# MEGA2560_Rev3e.net
KiCad netlist of a schematic drawn in EAGLE
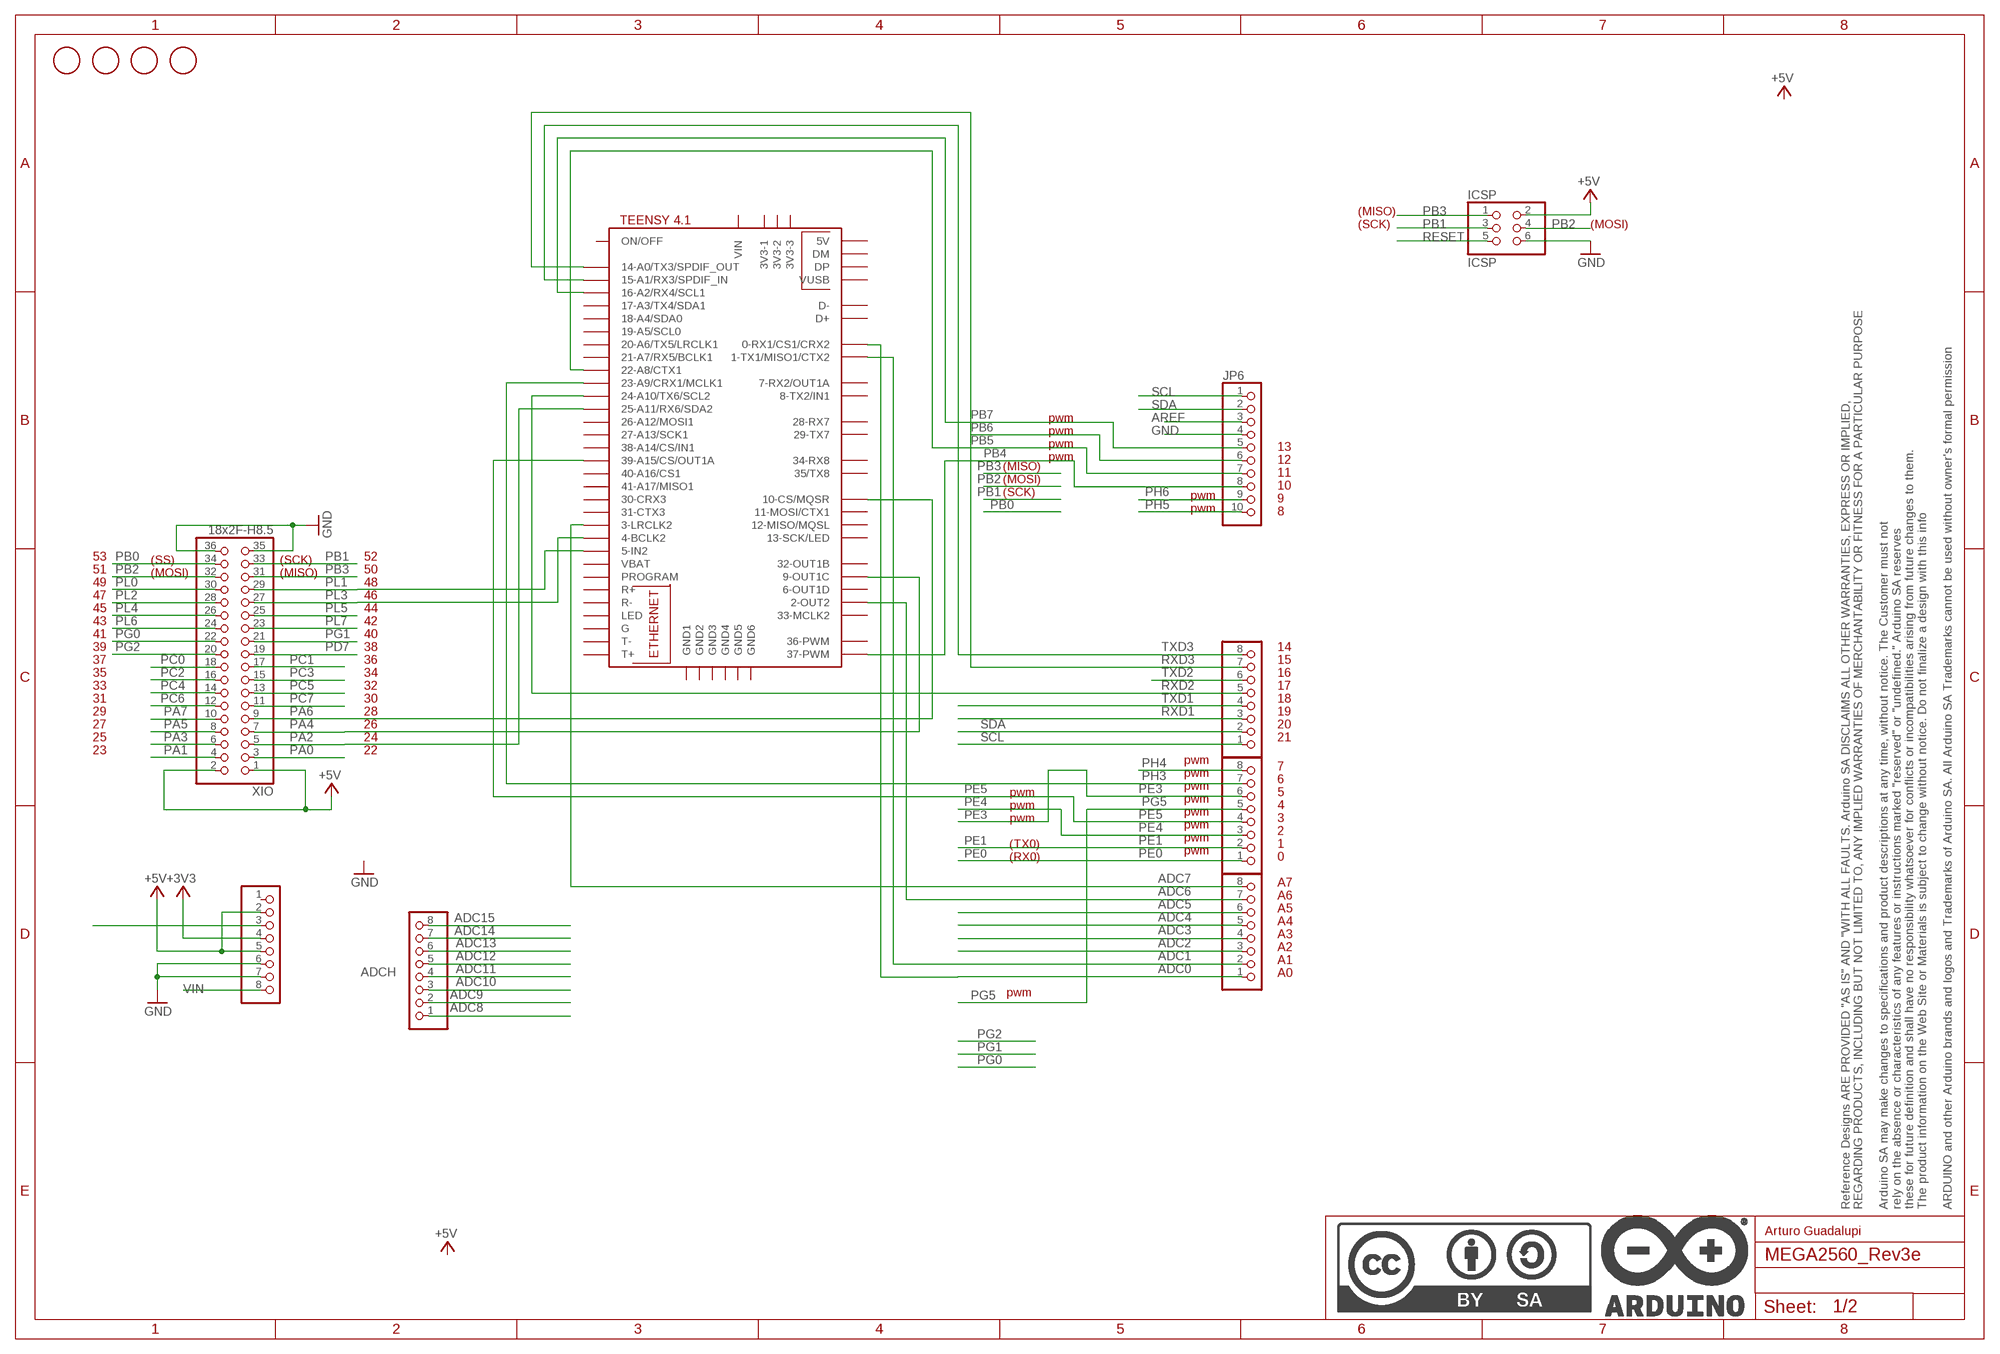
[diagram p0: schematic, sheet 1]
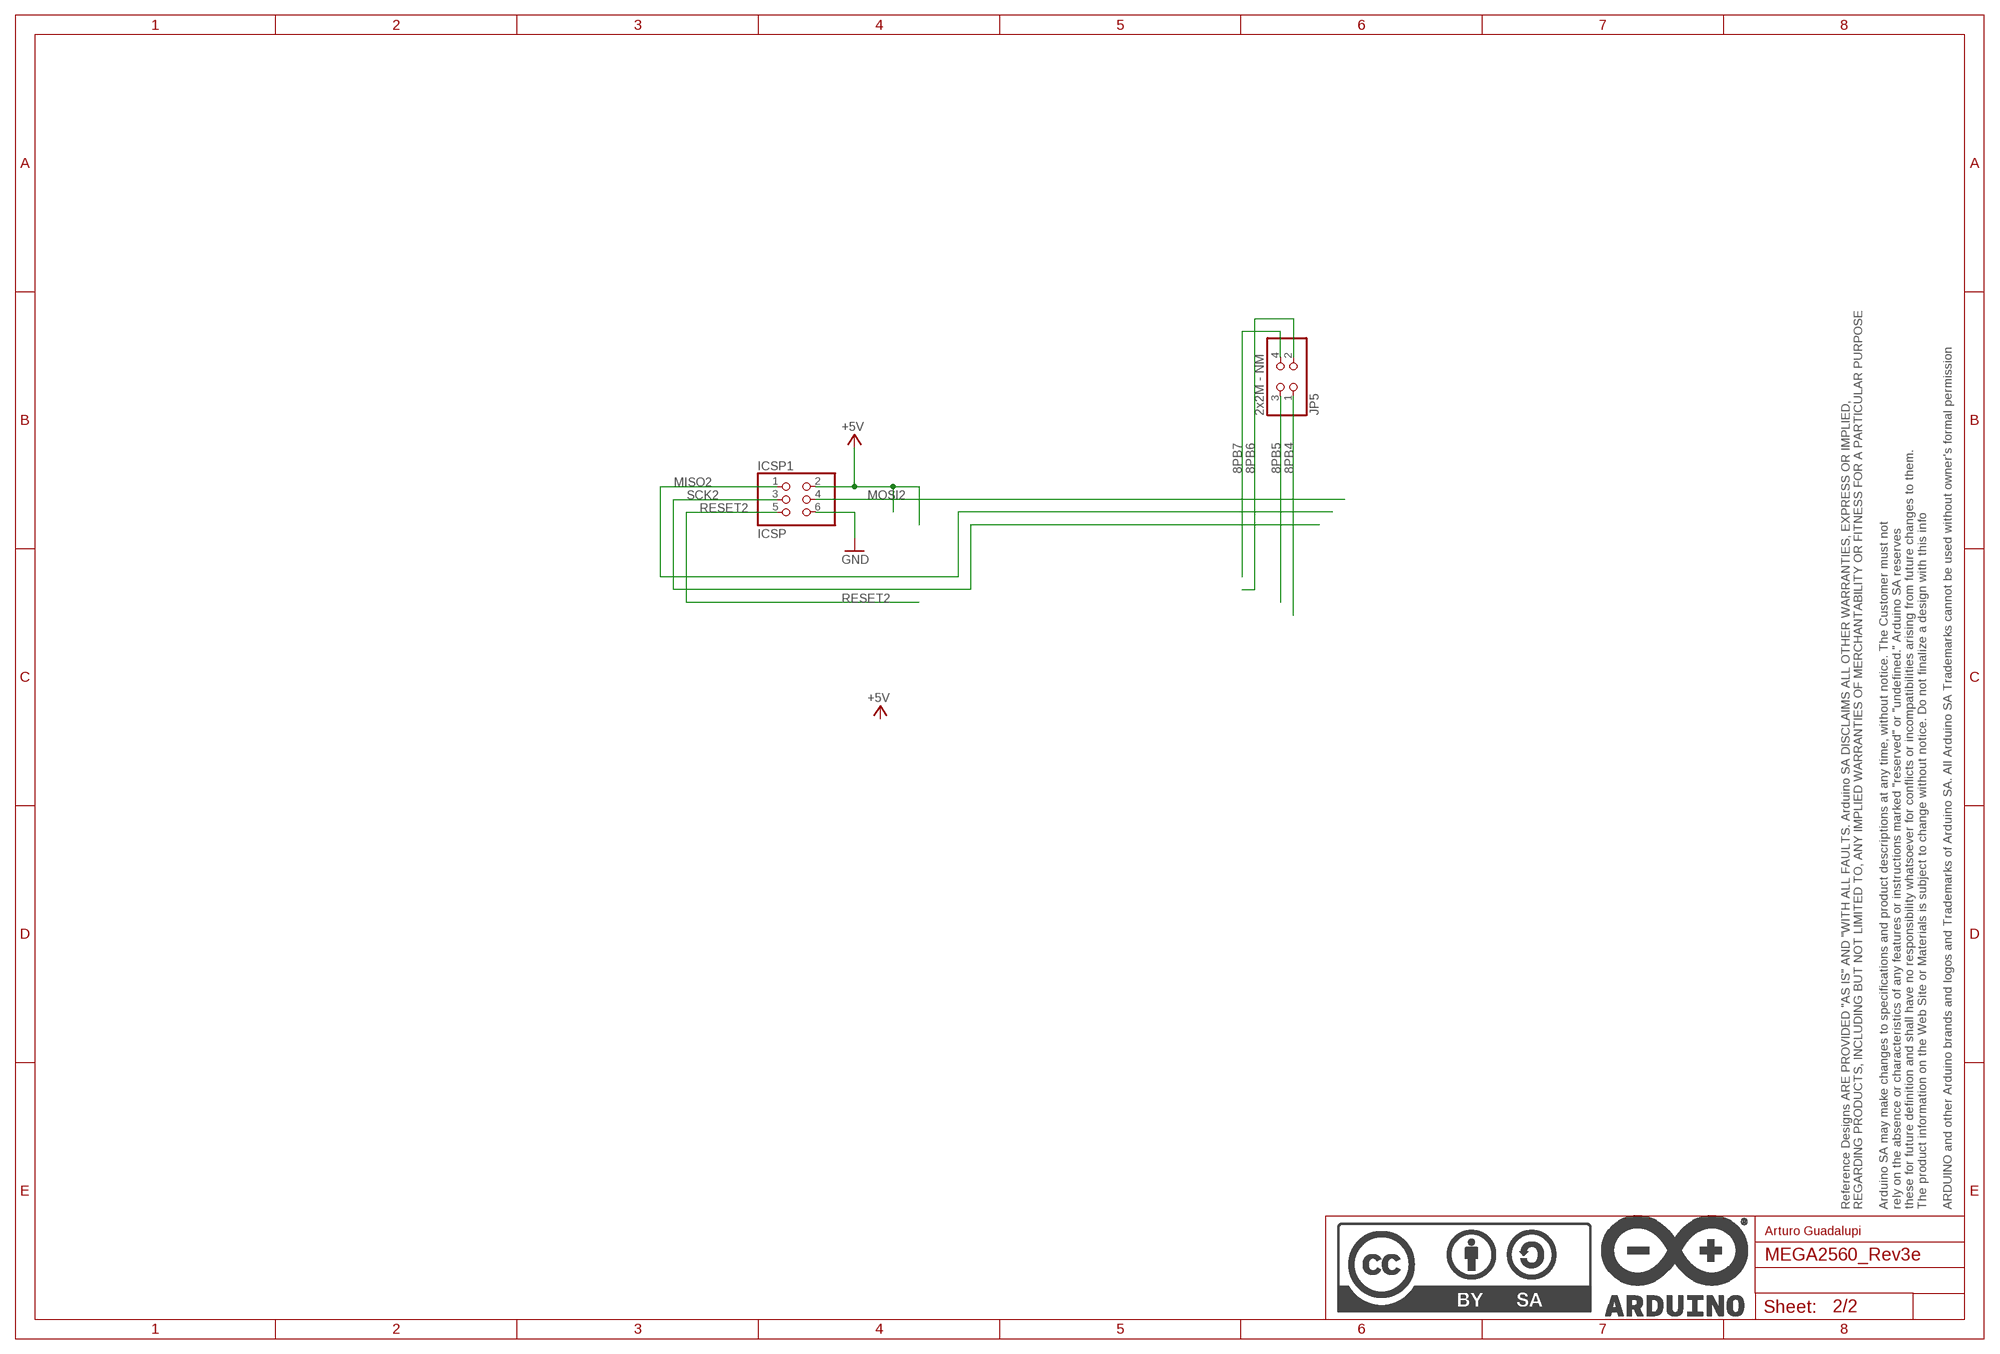
[diagram p1: schematic, sheet 2]

(export (version "E")
  (design (tool "Eeschema 10.0.6"))
  (components
    (comp (ref "ICSP1")
      (value "ICSP")
      (footprint "eagle-import:2X03")
      (fields (field (name "PART_NUMBER") "PH254-203DF118A00V"))
      (libsource (lib "eagle-import") (part "0114_PH254-203DF118A00V"))
    )
    (comp (ref "JP5")
      (value "2x2M - NM")
      (footprint "eagle-import:2X02")
      (libsource (lib "eagle-import") (part "PINHD-2X2"))
    )
    (comp (ref "U$2")
      (value "DNP")
      (footprint "eagle-import:FRAME")
      (libsource (lib "eagle-import") (part "A3-FRAME"))
    )
    (comp (ref "ADCH")
      (value "FH254-108DF08500V")
      (footprint "eagle-import:1X08")
      (libsource (lib "eagle-import") (part "0058_FH254-108DF08500V"))
    )
    (comp (ref "ADCL")
      (value "FH254-108DF08500V")
      (footprint "eagle-import:1X08")
      (libsource (lib "eagle-import") (part "0058_FH254-108DF08500V"))
    )
    (comp (ref "COMMUNICATION")
      (value "FH254-108DF08500V")
      (footprint "eagle-import:1X08")
      (libsource (lib "eagle-import") (part "0058_FH254-108DF08500V"))
    )
    (comp (ref "FD1")
      (value "FIDUCIALMOUNT")
      (footprint "eagle-import:FIDUCIA-MOUNT")
      (libsource (lib "eagle-import") (part "FIDUCIALMOUNT"))
    )
    (comp (ref "FD2")
      (value "FIDUCIALMOUNT")
      (footprint "eagle-import:FIDUCIA-MOUNT")
      (libsource (lib "eagle-import") (part "FIDUCIALMOUNT"))
    )
    (comp (ref "FD3")
      (value "FIDUCIALMOUNT")
      (footprint "eagle-import:FIDUCIA-MOUNT")
      (libsource (lib "eagle-import") (part "FIDUCIALMOUNT"))
    )
    (comp (ref "FD4")
      (value "FIDUCIALMOUNT")
      (footprint "eagle-import:FIDUCIA-MOUNT")
      (libsource (lib "eagle-import") (part "FIDUCIALMOUNT"))
    )
    (comp (ref "ICSP")
      (value "ICSP")
      (footprint "eagle-import:2X03")
      (fields (field (name "PART_NUMBER") "PH254-203DF118A00V"))
      (libsource (lib "eagle-import") (part "0114_PH254-203DF118A00V"))
    )
    (comp (ref "JP6")
      (value "FH254-110DF08500V")
      (footprint "eagle-import:1X10")
      (fields (field (name "PART_NUMBER") "FH254-110DF08500T30"))
      (libsource (lib "eagle-import") (part "1216_FH254-110DF08500T30"))
    )
    (comp (ref "POWER")
      (value "FH254-108DF08500V")
      (footprint "eagle-import:1X08")
      (fields (field (name "PART_NUMBER") "FH254-108DF08500T21"))
      (libsource (lib "eagle-import") (part "1217_FH254-108DF08500T21"))
    )
    (comp (ref "PWML")
      (value "FH254-108DF08500V")
      (footprint "eagle-import:1X08")
      (fields (field (name "PART_NUMBER") "FH254-108DF08500T20"))
      (libsource (lib "eagle-import") (part "1218_FH254-108DF08500T20"))
    )
    (comp (ref "U$1")
      (value "DNP")
      (footprint "eagle-import:FRAME")
      (libsource (lib "eagle-import") (part "A3-FRAME"))
    )
    (comp (ref "U$3")
      (value "TEENSY41")
      (footprint "eagle-import:TEENSY41")
      (libsource (lib "eagle-import") (part "TEENSY41"))
    )
    (comp (ref "XIO")
      (value "18x2F-H8.5")
      (footprint "eagle-import:2X18")
      (fields (field (name "PART_NUMBER") "FH254-218DF08500V"))
      (libsource (lib "eagle-import") (part "0060_FH254-218DF08500V"))
    )
  )
  (nets
    (net (code "1") (name "+3V3") (class "Default")
      (node (ref "POWER") (pin "4") (pinfunction "4_4") (pintype "passive"))
    )
    (net (code "2") (name "+5V") (class "Default")
      (node (ref "ICSP") (pin "2") (pinfunction "2_2") (pintype "passive"))
      (node (ref "ICSP1") (pin "2") (pinfunction "2_2") (pintype "passive"))
      (node (ref "POWER") (pin "2") (pinfunction "2_2") (pintype "passive"))
      (node (ref "POWER") (pin "5") (pinfunction "5_5") (pintype "passive"))
      (node (ref "XIO") (pin "1") (pinfunction "1_1") (pintype "passive"))
      (node (ref "XIO") (pin "2") (pinfunction "2_2") (pintype "passive"))
    )
    (net (code "3") (name "8PB4") (class "Default")
      (node (ref "JP5") (pin "1") (pinfunction "1_1") (pintype "passive"))
    )
    (net (code "4") (name "8PB5") (class "Default")
      (node (ref "JP5") (pin "3") (pinfunction "3_3") (pintype "passive"))
    )
    (net (code "5") (name "8PB6") (class "Default")
      (node (ref "JP5") (pin "2") (pinfunction "2_2") (pintype "passive"))
    )
    (net (code "6") (name "8PB7") (class "Default")
      (node (ref "JP5") (pin "4") (pinfunction "4_4") (pintype "passive"))
    )
    (net (code "7") (name "ADC0") (class "Default")
      (node (ref "ADCL") (pin "1") (pinfunction "1_1") (pintype "passive"))
      (node (ref "U$3") (pin "0-RX1/CS1/CRX2") (pinfunction "0-RX1/CS1/CRX2_0-RX1/CS1/CRX2") (pintype "bidirectional"))
    )
    (net (code "8") (name "ADC1") (class "Default")
      (node (ref "ADCL") (pin "2") (pinfunction "2_2") (pintype "passive"))
      (node (ref "U$3") (pin "1-TX1/MISO1/CTX2") (pinfunction "1-TX1/MISO1/CTX2_1-TX1/MISO1/CTX2") (pintype "bidirectional"))
    )
    (net (code "9") (name "ADC2") (class "Default")
      (node (ref "ADCL") (pin "3") (pinfunction "3_3") (pintype "passive"))
    )
    (net (code "10") (name "ADC3") (class "Default")
      (node (ref "ADCL") (pin "4") (pinfunction "4_4") (pintype "passive"))
    )
    (net (code "11") (name "ADC4") (class "Default")
      (node (ref "ADCL") (pin "5") (pinfunction "5_5") (pintype "passive"))
    )
    (net (code "12") (name "ADC5") (class "Default")
      (node (ref "ADCL") (pin "6") (pinfunction "6_6") (pintype "passive"))
    )
    (net (code "13") (name "ADC6") (class "Default")
      (node (ref "ADCL") (pin "7") (pinfunction "7_7") (pintype "passive"))
      (node (ref "U$3") (pin "2-OUT2") (pinfunction "2-OUT2_2-OUT2") (pintype "bidirectional"))
    )
    (net (code "14") (name "ADC7") (class "Default")
      (node (ref "ADCL") (pin "8") (pinfunction "8_8") (pintype "passive"))
      (node (ref "U$3") (pin "3-LRCLK2") (pinfunction "3-LRCLK2_3-LRCLK2") (pintype "bidirectional"))
    )
    (net (code "15") (name "ADC8") (class "Default")
      (node (ref "ADCH") (pin "1") (pinfunction "1_1") (pintype "passive"))
    )
    (net (code "16") (name "ADC9") (class "Default")
      (node (ref "ADCH") (pin "2") (pinfunction "2_2") (pintype "passive"))
    )
    (net (code "17") (name "ADC10") (class "Default")
      (node (ref "ADCH") (pin "3") (pinfunction "3_3") (pintype "passive"))
    )
    (net (code "18") (name "ADC11") (class "Default")
      (node (ref "ADCH") (pin "4") (pinfunction "4_4") (pintype "passive"))
    )
    (net (code "19") (name "ADC12") (class "Default")
      (node (ref "ADCH") (pin "5") (pinfunction "5_5") (pintype "passive"))
    )
    (net (code "20") (name "ADC13") (class "Default")
      (node (ref "ADCH") (pin "6") (pinfunction "6_6") (pintype "passive"))
    )
    (net (code "21") (name "ADC14") (class "Default")
      (node (ref "ADCH") (pin "7") (pinfunction "7_7") (pintype "passive"))
    )
    (net (code "22") (name "ADC15") (class "Default")
      (node (ref "ADCH") (pin "8") (pinfunction "8_8") (pintype "passive"))
    )
    (net (code "23") (name "AREF") (class "Default")
      (node (ref "JP6") (pin "3") (pinfunction "3_3") (pintype "passive"))
    )
    (net (code "24") (name "GND") (class "Default")
      (node (ref "ICSP") (pin "6") (pinfunction "6_6") (pintype "passive"))
      (node (ref "ICSP1") (pin "6") (pinfunction "6_6") (pintype "passive"))
      (node (ref "JP6") (pin "4") (pinfunction "4_4") (pintype "passive"))
      (node (ref "POWER") (pin "6") (pinfunction "6_6") (pintype "passive"))
      (node (ref "POWER") (pin "7") (pinfunction "7_7") (pintype "passive"))
      (node (ref "XIO") (pin "35") (pinfunction "35_35") (pintype "passive"))
      (node (ref "XIO") (pin "36") (pinfunction "36_36") (pintype "passive"))
    )
    (net (code "25") (name "MISO2") (class "Default")
      (node (ref "ICSP1") (pin "1") (pinfunction "1_1") (pintype "passive"))
    )
    (net (code "26") (name "MOSI2") (class "Default")
      (node (ref "ICSP1") (pin "4") (pinfunction "4_4") (pintype "passive"))
    )
    (net (code "27") (name "PA0") (class "Default")
      (node (ref "XIO") (pin "3") (pinfunction "3_3") (pintype "passive"))
    )
    (net (code "28") (name "PA1") (class "Default")
      (node (ref "XIO") (pin "4") (pinfunction "4_4") (pintype "passive"))
    )
    (net (code "29") (name "PA2") (class "Default")
      (node (ref "U$3") (pin "25-A11/RX6/SDA2") (pinfunction "25-A11/RX6/SDA2_25-A11/RX6/SDA2") (pintype "bidirectional"))
      (node (ref "XIO") (pin "5") (pinfunction "5_5") (pintype "passive"))
    )
    (net (code "30") (name "PA3") (class "Default")
      (node (ref "XIO") (pin "6") (pinfunction "6_6") (pintype "passive"))
    )
    (net (code "31") (name "PA4") (class "Default")
      (node (ref "U$3") (pin "9-OUT1C") (pinfunction "9-OUT1C_9-OUT1C") (pintype "bidirectional"))
      (node (ref "XIO") (pin "7") (pinfunction "7_7") (pintype "passive"))
    )
    (net (code "32") (name "PA5") (class "Default")
      (node (ref "XIO") (pin "8") (pinfunction "8_8") (pintype "passive"))
    )
    (net (code "33") (name "PA6") (class "Default")
      (node (ref "U$3") (pin "10-CS\\MQSR") (pinfunction "10-CS/MQSR_10-CS\\MQSR") (pintype "bidirectional"))
      (node (ref "XIO") (pin "9") (pinfunction "9_9") (pintype "passive"))
    )
    (net (code "34") (name "PA7") (class "Default")
      (node (ref "XIO") (pin "10") (pinfunction "10_10") (pintype "passive"))
    )
    (net (code "35") (name "PB0") (class "Default")
      (node (ref "XIO") (pin "34") (pinfunction "34_34") (pintype "passive"))
    )
    (net (code "36") (name "PB1") (class "Default")
      (node (ref "ICSP") (pin "3") (pinfunction "3_3") (pintype "passive"))
      (node (ref "XIO") (pin "33") (pinfunction "33_33") (pintype "passive"))
    )
    (net (code "37") (name "PB2") (class "Default")
      (node (ref "ICSP") (pin "4") (pinfunction "4_4") (pintype "passive"))
      (node (ref "XIO") (pin "32") (pinfunction "32_32") (pintype "passive"))
    )
    (net (code "38") (name "PB3") (class "Default")
      (node (ref "ICSP") (pin "1") (pinfunction "1_1") (pintype "passive"))
      (node (ref "XIO") (pin "31") (pinfunction "31_31") (pintype "passive"))
    )
    (net (code "39") (name "PB4") (class "Default")
      (node (ref "JP6") (pin "8") (pinfunction "8_8") (pintype "passive"))
      (node (ref "U$3") (pin "37-PWM") (pinfunction "37-PWM_37-PWM") (pintype "bidirectional"))
    )
    (net (code "40") (name "PB5") (class "Default")
      (node (ref "JP6") (pin "7") (pinfunction "7_7") (pintype "passive"))
      (node (ref "U$3") (pin "22-A8/CTX1") (pinfunction "22-A8/CTX1_22-A8/CTX1") (pintype "bidirectional"))
    )
    (net (code "41") (name "PB6") (class "Default")
      (node (ref "JP6") (pin "6") (pinfunction "6_6") (pintype "passive"))
    )
    (net (code "42") (name "PB7") (class "Default")
      (node (ref "JP6") (pin "5") (pinfunction "5_5") (pintype "passive"))
      (node (ref "U$3") (pin "16-A2/RX4/SCL1") (pinfunction "16-A2/RX4/SCL1_16-A2/RX4/SCL1") (pintype "bidirectional"))
    )
    (net (code "43") (name "PC0") (class "Default")
      (node (ref "XIO") (pin "18") (pinfunction "18_18") (pintype "passive"))
    )
    (net (code "44") (name "PC1") (class "Default")
      (node (ref "XIO") (pin "17") (pinfunction "17_17") (pintype "passive"))
    )
    (net (code "45") (name "PC2") (class "Default")
      (node (ref "XIO") (pin "16") (pinfunction "16_16") (pintype "passive"))
    )
    (net (code "46") (name "PC3") (class "Default")
      (node (ref "XIO") (pin "15") (pinfunction "15_15") (pintype "passive"))
    )
    (net (code "47") (name "PC4") (class "Default")
      (node (ref "XIO") (pin "14") (pinfunction "14_14") (pintype "passive"))
    )
    (net (code "48") (name "PC5") (class "Default")
      (node (ref "XIO") (pin "13") (pinfunction "13_13") (pintype "passive"))
    )
    (net (code "49") (name "PC6") (class "Default")
      (node (ref "XIO") (pin "12") (pinfunction "12_12") (pintype "passive"))
    )
    (net (code "50") (name "PC7") (class "Default")
      (node (ref "XIO") (pin "11") (pinfunction "11_11") (pintype "passive"))
    )
    (net (code "51") (name "PD7") (class "Default")
      (node (ref "XIO") (pin "19") (pinfunction "19_19") (pintype "passive"))
    )
    (net (code "52") (name "PE0") (class "Default")
      (node (ref "PWML") (pin "1") (pinfunction "1_1") (pintype "passive"))
    )
    (net (code "53") (name "PE1") (class "Default")
      (node (ref "PWML") (pin "2") (pinfunction "2_2") (pintype "passive"))
    )
    (net (code "54") (name "PE3") (class "Default")
      (node (ref "PWML") (pin "6") (pinfunction "6_6") (pintype "passive"))
    )
    (net (code "55") (name "PE4") (class "Default")
      (node (ref "PWML") (pin "3") (pinfunction "3_3") (pintype "passive"))
    )
    (net (code "56") (name "PE5") (class "Default")
      (node (ref "PWML") (pin "4") (pinfunction "4_4") (pintype "passive"))
      (node (ref "U$3") (pin "39-A15/CS/OUT1A") (pinfunction "39-A15/CS/OUT1A_39-A15/CS/OUT1A") (pintype "bidirectional"))
    )
    (net (code "57") (name "PG0") (class "Default")
      (node (ref "XIO") (pin "22") (pinfunction "22_22") (pintype "passive"))
    )
    (net (code "58") (name "PG1") (class "Default")
      (node (ref "XIO") (pin "21") (pinfunction "21_21") (pintype "passive"))
    )
    (net (code "59") (name "PG2") (class "Default")
      (node (ref "XIO") (pin "20") (pinfunction "20_20") (pintype "passive"))
    )
    (net (code "60") (name "PG5") (class "Default")
      (node (ref "PWML") (pin "5") (pinfunction "5_5") (pintype "passive"))
    )
    (net (code "61") (name "PH3") (class "Default")
      (node (ref "PWML") (pin "7") (pinfunction "7_7") (pintype "passive"))
      (node (ref "U$3") (pin "23-A9/CRX1/MCLK1") (pinfunction "23-A9/CRX1/MCLK1_23-A9/CRX1/MCLK1") (pintype "bidirectional"))
    )
    (net (code "62") (name "PH4") (class "Default")
      (node (ref "PWML") (pin "8") (pinfunction "8_8") (pintype "passive"))
    )
    (net (code "63") (name "PH5") (class "Default")
      (node (ref "JP6") (pin "10") (pinfunction "10_10") (pintype "passive"))
    )
    (net (code "64") (name "PH6") (class "Default")
      (node (ref "JP6") (pin "9") (pinfunction "9_9") (pintype "passive"))
    )
    (net (code "65") (name "PL0") (class "Default")
      (node (ref "XIO") (pin "30") (pinfunction "30_30") (pintype "passive"))
    )
    (net (code "66") (name "PL1") (class "Default")
      (node (ref "U$3") (pin "5-IN2") (pinfunction "5-IN2_5-IN2") (pintype "bidirectional"))
      (node (ref "XIO") (pin "29") (pinfunction "29_29") (pintype "passive"))
    )
    (net (code "67") (name "PL2") (class "Default")
      (node (ref "XIO") (pin "28") (pinfunction "28_28") (pintype "passive"))
    )
    (net (code "68") (name "PL3") (class "Default")
      (node (ref "U$3") (pin "4-BCLK2") (pinfunction "4-BCLK2_4-BCLK2") (pintype "bidirectional"))
      (node (ref "XIO") (pin "27") (pinfunction "27_27") (pintype "passive"))
    )
    (net (code "69") (name "PL4") (class "Default")
      (node (ref "XIO") (pin "26") (pinfunction "26_26") (pintype "passive"))
    )
    (net (code "70") (name "PL5") (class "Default")
      (node (ref "XIO") (pin "25") (pinfunction "25_25") (pintype "passive"))
    )
    (net (code "71") (name "PL6") (class "Default")
      (node (ref "XIO") (pin "24") (pinfunction "24_24") (pintype "passive"))
    )
    (net (code "72") (name "PL7") (class "Default")
      (node (ref "XIO") (pin "23") (pinfunction "23_23") (pintype "passive"))
    )
    (net (code "73") (name "RESET") (class "Default")
      (node (ref "ICSP") (pin "5") (pinfunction "5_5") (pintype "passive"))
      (node (ref "POWER") (pin "3") (pinfunction "3_3") (pintype "passive"))
    )
    (net (code "74") (name "RESET2") (class "Default")
      (node (ref "ICSP1") (pin "5") (pinfunction "5_5") (pintype "passive"))
    )
    (net (code "75") (name "RXD1") (class "Default")
      (node (ref "COMMUNICATION") (pin "3") (pinfunction "3_3") (pintype "passive"))
    )
    (net (code "76") (name "RXD2") (class "Default")
      (node (ref "COMMUNICATION") (pin "5") (pinfunction "5_5") (pintype "passive"))
      (node (ref "U$3") (pin "24-A10/TX6/SCL2") (pinfunction "24-A10/TX6/SCL2_24-A10/TX6/SCL2") (pintype "bidirectional"))
    )
    (net (code "77") (name "RXD3") (class "Default")
      (node (ref "COMMUNICATION") (pin "7") (pinfunction "7_7") (pintype "passive"))
      (node (ref "U$3") (pin "14-A0/TX3/SPDIF_OUT") (pinfunction "14-A0/TX3/SPDIF_OUT_14-A0/TX3/SPDIF_OUT") (pintype "bidirectional"))
    )
    (net (code "78") (name "SCK2") (class "Default")
      (node (ref "ICSP1") (pin "3") (pinfunction "3_3") (pintype "passive"))
    )
    (net (code "79") (name "SCL") (class "Default")
      (node (ref "COMMUNICATION") (pin "1") (pinfunction "1_1") (pintype "passive"))
      (node (ref "JP6") (pin "1") (pinfunction "1_1") (pintype "passive"))
    )
    (net (code "80") (name "SDA") (class "Default")
      (node (ref "COMMUNICATION") (pin "2") (pinfunction "2_2") (pintype "passive"))
      (node (ref "JP6") (pin "2") (pinfunction "2_2") (pintype "passive"))
    )
    (net (code "81") (name "TXD1") (class "Default")
      (node (ref "COMMUNICATION") (pin "4") (pinfunction "4_4") (pintype "passive"))
    )
    (net (code "82") (name "TXD2") (class "Default")
      (node (ref "COMMUNICATION") (pin "6") (pinfunction "6_6") (pintype "passive"))
    )
    (net (code "83") (name "TXD3") (class "Default")
      (node (ref "COMMUNICATION") (pin "8") (pinfunction "8_8") (pintype "passive"))
      (node (ref "U$3") (pin "15-A1/RX3/SPDIF_IN") (pinfunction "15-A1/RX3/SPDIF_IN_15-A1/RX3/SPDIF_IN") (pintype "bidirectional"))
    )
    (net (code "84") (name "VIN") (class "Default")
      (node (ref "POWER") (pin "8") (pinfunction "8_8") (pintype "passive"))
    )
    (net (code "85") (name "unconnected-(POWER-Pad1)") (class "Default")
      (node (ref "POWER") (pin "1") (pinfunction "1_1") (pintype "passive"))
    )
    (net (code "86") (name "unconnected-(U$3-5V-Pad+5V)") (class "Default")
      (node (ref "U$3") (pin "+5V") (pinfunction "5V_+5V") (pintype "bidirectional"))
    )
    (net (code "87") (name "unconnected-(U$3-35{slash}TX8-Pad35-TX8)") (class "Default")
      (node (ref "U$3") (pin "35-TX8") (pinfunction "35/TX8_35-TX8") (pintype "bidirectional"))
    )
    (net (code "88") (name "unconnected-(U$3-Pad3V3-1)") (class "Default")
      (node (ref "U$3") (pin "3V3-1") (pinfunction "3V3-1_3V3-1") (pintype "bidirectional"))
    )
    (net (code "89") (name "unconnected-(U$3-Pad3V3-2)") (class "Default")
      (node (ref "U$3") (pin "3V3-2") (pinfunction "3V3-2_3V3-2") (pintype "bidirectional"))
    )
    (net (code "90") (name "unconnected-(U$3-Pad3V3-3)") (class "Default")
      (node (ref "U$3") (pin "3V3-3") (pinfunction "3V3-3_3V3-3") (pintype "bidirectional"))
    )
    (net (code "91") (name "unconnected-(U$3-Pad6-OUT1D)") (class "Default")
      (node (ref "U$3") (pin "6-OUT1D") (pinfunction "6-OUT1D_6-OUT1D") (pintype "bidirectional"))
    )
    (net (code "92") (name "unconnected-(U$3-Pad7-RX2{slash}OUT1A)") (class "Default")
      (node (ref "U$3") (pin "7-RX2/OUT1A") (pinfunction "7-RX2/OUT1A_7-RX2/OUT1A") (pintype "bidirectional"))
    )
    (net (code "93") (name "unconnected-(U$3-Pad8-TX2{slash}IN1)") (class "Default")
      (node (ref "U$3") (pin "8-TX2/IN1") (pinfunction "8-TX2/IN1_8-TX2/IN1") (pintype "bidirectional"))
    )
    (net (code "94") (name "unconnected-(U$3-Pad11-MOSI{slash}CTX1)") (class "Default")
      (node (ref "U$3") (pin "11-MOSI/CTX1") (pinfunction "11-MOSI/CTX1_11-MOSI/CTX1") (pintype "bidirectional"))
    )
    (net (code "95") (name "unconnected-(U$3-Pad12-MISO{slash}MQSL)") (class "Default")
      (node (ref "U$3") (pin "12-MISO/MQSL") (pinfunction "12-MISO/MQSL_12-MISO/MQSL") (pintype "bidirectional"))
    )
    (net (code "96") (name "unconnected-(U$3-Pad13-SCK{slash}LED)") (class "Default")
      (node (ref "U$3") (pin "13-SCK/LED") (pinfunction "13-SCK/LED_13-SCK/LED") (pintype "bidirectional"))
    )
    (net (code "97") (name "unconnected-(U$3-Pad17-A3{slash}TX4{slash}SDA1)") (class "Default")
      (node (ref "U$3") (pin "17-A3/TX4/SDA1") (pinfunction "17-A3/TX4/SDA1_17-A3/TX4/SDA1") (pintype "bidirectional"))
    )
    (net (code "98") (name "unconnected-(U$3-Pad18-A4{slash}SDA0)") (class "Default")
      (node (ref "U$3") (pin "18-A4/SDA0") (pinfunction "18-A4/SDA0_18-A4/SDA0") (pintype "bidirectional"))
    )
    (net (code "99") (name "unconnected-(U$3-Pad19-A5{slash}SCL0)") (class "Default")
      (node (ref "U$3") (pin "19-A5/SCL0") (pinfunction "19-A5/SCL0_19-A5/SCL0") (pintype "bidirectional"))
    )
    (net (code "100") (name "unconnected-(U$3-Pad20-A6{slash}TX5{slash}LRCLK1)") (class "Default")
      (node (ref "U$3") (pin "20-A6/TX5/LRCLK1") (pinfunction "20-A6/TX5/LRCLK1_20-A6/TX5/LRCLK1") (pintype "bidirectional"))
    )
    (net (code "101") (name "unconnected-(U$3-Pad21-A7{slash}RX5{slash}BCLK1)") (class "Default")
      (node (ref "U$3") (pin "21-A7/RX5/BCLK1") (pinfunction "21-A7/RX5/BCLK1_21-A7/RX5/BCLK1") (pintype "bidirectional"))
    )
    (net (code "102") (name "unconnected-(U$3-Pad26-A12{slash}MOSI1)") (class "Default")
      (node (ref "U$3") (pin "26-A12/MOSI1") (pinfunction "26-A12/MOSI1_26-A12/MOSI1") (pintype "bidirectional"))
    )
    (net (code "103") (name "unconnected-(U$3-Pad27-A13{slash}SCK1)") (class "Default")
      (node (ref "U$3") (pin "27-A13/SCK1") (pinfunction "27-A13/SCK1_27-A13/SCK1") (pintype "bidirectional"))
    )
    (net (code "104") (name "unconnected-(U$3-Pad28-RX7)") (class "Default")
      (node (ref "U$3") (pin "28-RX7") (pinfunction "28-RX7_28-RX7") (pintype "bidirectional"))
    )
    (net (code "105") (name "unconnected-(U$3-Pad29-TX7)") (class "Default")
      (node (ref "U$3") (pin "29-TX7") (pinfunction "29-TX7_29-TX7") (pintype "bidirectional"))
    )
    (net (code "106") (name "unconnected-(U$3-Pad30-CRX3)") (class "Default")
      (node (ref "U$3") (pin "30-CRX3") (pinfunction "30-CRX3_30-CRX3") (pintype "bidirectional"))
    )
    (net (code "107") (name "unconnected-(U$3-Pad31-CTX3)") (class "Default")
      (node (ref "U$3") (pin "31-CTX3") (pinfunction "31-CTX3_31-CTX3") (pintype "bidirectional"))
    )
    (net (code "108") (name "unconnected-(U$3-Pad32-OUT1B)") (class "Default")
      (node (ref "U$3") (pin "32-OUT1B") (pinfunction "32-OUT1B_32-OUT1B") (pintype "bidirectional"))
    )
    (net (code "109") (name "unconnected-(U$3-Pad33-MCLK2)") (class "Default")
      (node (ref "U$3") (pin "33-MCLK2") (pinfunction "33-MCLK2_33-MCLK2") (pintype "bidirectional"))
    )
    (net (code "110") (name "unconnected-(U$3-Pad34-RX8)") (class "Default")
      (node (ref "U$3") (pin "34-RX8") (pinfunction "34-RX8_34-RX8") (pintype "bidirectional"))
    )
    (net (code "111") (name "unconnected-(U$3-Pad36-PWM)") (class "Default")
      (node (ref "U$3") (pin "36-PWM") (pinfunction "36-PWM_36-PWM") (pintype "bidirectional"))
    )
    (net (code "112") (name "unconnected-(U$3-Pad38-A14{slash}CS{slash}IN1)") (class "Default")
      (node (ref "U$3") (pin "38-A14/CS/IN1") (pinfunction "38-A14/CS/IN1_38-A14/CS/IN1") (pintype "bidirectional"))
    )
    (net (code "113") (name "unconnected-(U$3-Pad40-A16{slash}CS1)") (class "Default")
      (node (ref "U$3") (pin "40-A16/CS1") (pinfunction "40-A16/CS1_40-A16/CS1") (pintype "bidirectional"))
    )
    (net (code "114") (name "unconnected-(U$3-Pad41-A17{slash}MISO1)") (class "Default")
      (node (ref "U$3") (pin "41-A17/MISO1") (pinfunction "41-A17/MISO1_41-A17/MISO1") (pintype "bidirectional"))
    )
    (net (code "115") (name "unconnected-(U$3-PadD+)") (class "Default")
      (node (ref "U$3") (pin "D+") (pinfunction "D+_D+") (pintype "bidirectional"))
    )
    (net (code "116") (name "unconnected-(U$3-PadD-)") (class "Default")
      (node (ref "U$3") (pin "D-") (pinfunction "D-_D-") (pintype "bidirectional"))
    )
    (net (code "117") (name "unconnected-(U$3-PadDM)") (class "Default")
      (node (ref "U$3") (pin "DM") (pinfunction "DM_DM") (pintype "bidirectional"))
    )
    (net (code "118") (name "unconnected-(U$3-PadDP)") (class "Default")
      (node (ref "U$3") (pin "DP") (pinfunction "DP_DP") (pintype "bidirectional"))
    )
    (net (code "119") (name "unconnected-(U$3-PadG)") (class "Default")
      (node (ref "U$3") (pin "G") (pinfunction "G_G") (pintype "bidirectional"))
    )
    (net (code "120") (name "unconnected-(U$3-PadGND1)") (class "Default")
      (node (ref "U$3") (pin "GND1") (pinfunction "GND1_GND1") (pintype "bidirectional"))
    )
    (net (code "121") (name "unconnected-(U$3-PadGND2)") (class "Default")
      (node (ref "U$3") (pin "GND2") (pinfunction "GND2_GND2") (pintype "bidirectional"))
    )
    (net (code "122") (name "unconnected-(U$3-PadGND3)") (class "Default")
      (node (ref "U$3") (pin "GND3") (pinfunction "GND3_GND3") (pintype "bidirectional"))
    )
    (net (code "123") (name "unconnected-(U$3-PadGND4)") (class "Default")
      (node (ref "U$3") (pin "GND4") (pinfunction "GND4_GND4") (pintype "bidirectional"))
    )
    (net (code "124") (name "unconnected-(U$3-PadGND5)") (class "Default")
      (node (ref "U$3") (pin "GND5") (pinfunction "GND5_GND5") (pintype "bidirectional"))
    )
    (net (code "125") (name "unconnected-(U$3-PadGND6)") (class "Default")
      (node (ref "U$3") (pin "GND6") (pinfunction "GND6_GND6") (pintype "bidirectional"))
    )
    (net (code "126") (name "unconnected-(U$3-PadLED)") (class "Default")
      (node (ref "U$3") (pin "LED") (pinfunction "LED_LED") (pintype "bidirectional"))
    )
    (net (code "127") (name "unconnected-(U$3-PadON{slash}OFF)") (class "Default")
      (node (ref "U$3") (pin "ON/OFF") (pinfunction "ON/OFF_ON/OFF") (pintype "bidirectional"))
    )
    (net (code "128") (name "unconnected-(U$3-PadPROGRAM)") (class "Default")
      (node (ref "U$3") (pin "PROGRAM") (pinfunction "PROGRAM_PROGRAM") (pintype "bidirectional"))
    )
    (net (code "129") (name "unconnected-(U$3-PadR+)") (class "Default")
      (node (ref "U$3") (pin "R+") (pinfunction "R+_R+") (pintype "bidirectional"))
    )
    (net (code "130") (name "unconnected-(U$3-PadR-)") (class "Default")
      (node (ref "U$3") (pin "R-") (pinfunction "R-_R-") (pintype "bidirectional"))
    )
    (net (code "131") (name "unconnected-(U$3-PadT+)") (class "Default")
      (node (ref "U$3") (pin "T+") (pinfunction "T+_T+") (pintype "bidirectional"))
    )
    (net (code "132") (name "unconnected-(U$3-PadT-)") (class "Default")
      (node (ref "U$3") (pin "T-") (pinfunction "T-_T-") (pintype "bidirectional"))
    )
    (net (code "133") (name "unconnected-(U$3-PadVBAT)") (class "Default")
      (node (ref "U$3") (pin "VBAT") (pinfunction "VBAT_VBAT") (pintype "bidirectional"))
    )
    (net (code "134") (name "unconnected-(U$3-PadVIN)") (class "Default")
      (node (ref "U$3") (pin "VIN") (pinfunction "VIN_VIN") (pintype "bidirectional"))
    )
    (net (code "135") (name "unconnected-(U$3-PadVUSB)") (class "Default")
      (node (ref "U$3") (pin "VUSB") (pinfunction "VUSB_VUSB") (pintype "bidirectional"))
    )
  )
)
